# SPI_LCD_Backpack.net
KiCad netlist of a schematic drawn in EAGLE
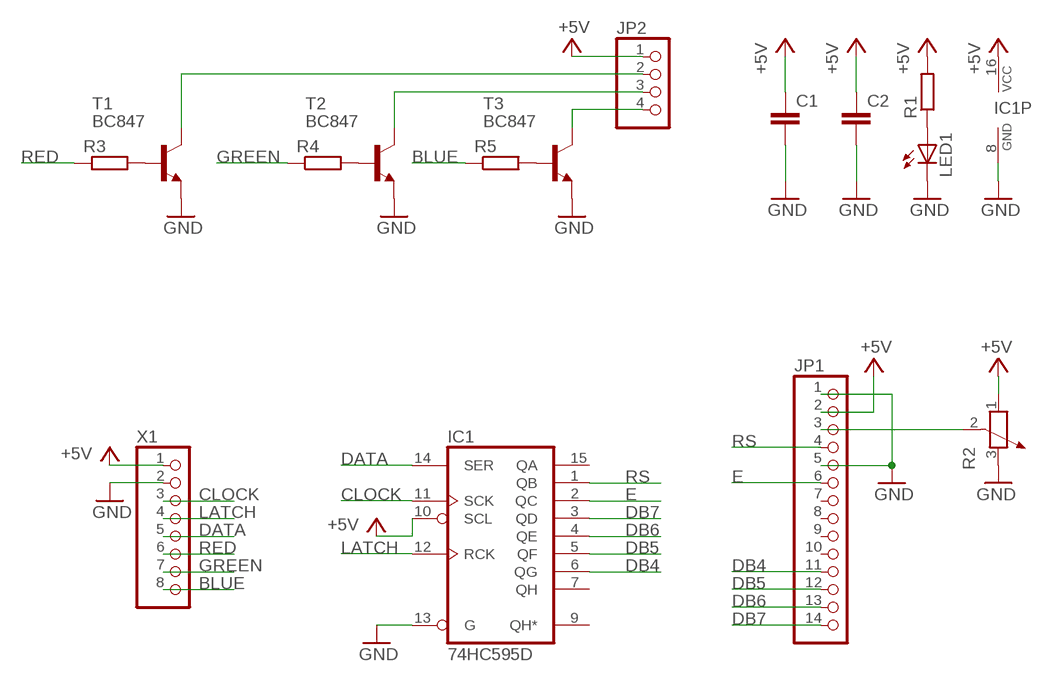
[diagram p0: schematic, sheet 1]

(export (version "E")
  (design (tool "Eeschema 10.0.6"))
  (components
    (comp (ref "C1")
      (value "C-EUC0805K")
      (footprint "eagle-import:C0805K")
      (libsource (lib "eagle-import") (part "C-EUC0805K"))
    )
    (comp (ref "C2")
      (value "C-EUC0805K")
      (footprint "eagle-import:C0805K")
      (libsource (lib "eagle-import") (part "C-EUC0805K"))
    )
    (comp (ref "IC1")
      (value "74HC595D")
      (footprint "eagle-import:SO16")
      (libsource (lib "eagle-import") (part "74595DHC"))
    )
    (comp (ref "JP1")
      (value "PINHD-1X14")
      (footprint "eagle-import:1X14")
      (libsource (lib "eagle-import") (part "PINHD-1X14"))
    )
    (comp (ref "JP2")
      (value "PINHD-1X4")
      (footprint "eagle-import:1X04")
      (libsource (lib "eagle-import") (part "PINHD-1X4"))
    )
    (comp (ref "LED1")
      (value "LED3MM")
      (footprint "eagle-import:LED3MM")
      (libsource (lib "eagle-import") (part "LED3MM"))
    )
    (comp (ref "R1")
      (value "R-EU_0805")
      (footprint "eagle-import:R0805")
      (libsource (lib "eagle-import") (part "R-EU_0805"))
    )
    (comp (ref "R2")
      (value "POTENTIOMETER_3386F")
      (footprint "eagle-import:3386F")
      (libsource (lib "eagle-import") (part "POTENTIOMETER_3386F"))
    )
    (comp (ref "R3")
      (value "R-EU_0805")
      (footprint "eagle-import:R0805")
      (libsource (lib "eagle-import") (part "R-EU_0805"))
    )
    (comp (ref "R4")
      (value "R-EU_0805")
      (footprint "eagle-import:R0805")
      (libsource (lib "eagle-import") (part "R-EU_0805"))
    )
    (comp (ref "R5")
      (value "R-EU_0805")
      (footprint "eagle-import:R0805")
      (libsource (lib "eagle-import") (part "R-EU_0805"))
    )
    (comp (ref "T1")
      (value "BC847")
      (footprint "eagle-import:SOT23")
      (libsource (lib "eagle-import") (part "BC847"))
    )
    (comp (ref "T2")
      (value "BC847")
      (footprint "eagle-import:SOT23")
      (libsource (lib "eagle-import") (part "BC847"))
    )
    (comp (ref "T3")
      (value "BC847")
      (footprint "eagle-import:SOT23")
      (libsource (lib "eagle-import") (part "BC847"))
    )
    (comp (ref "X1")
      (value "22-23-2081")
      (footprint "eagle-import:22-23-2081")
      (fields (field (name "MF") "MOLEX"))
      (libsource (lib "eagle-import") (part "22-23-2081"))
    )
  )
  (nets
    (net (code "1") (name "+5V") (class "Default")
      (node (ref "C1") (pin "1") (pinfunction "1_1") (pintype "passive"))
      (node (ref "C2") (pin "1") (pinfunction "1_1") (pintype "passive"))
      (node (ref "IC1") (pin "10") (pinfunction "SCL_10") (pintype "input"))
      (node (ref "IC1") (pin "16") (pinfunction "VCC_16") (pintype "power_in"))
      (node (ref "JP1") (pin "2") (pinfunction "2_2") (pintype "passive"))
      (node (ref "JP2") (pin "1") (pinfunction "1_1") (pintype "passive"))
      (node (ref "R1") (pin "2") (pinfunction "2_2") (pintype "passive"))
      (node (ref "R2") (pin "1") (pinfunction "1_1") (pintype "passive"))
      (node (ref "X1") (pin "1") (pinfunction "1_1") (pintype "passive"))
    )
    (net (code "2") (name "/BLUE") (class "Default")
      (node (ref "R5") (pin "1") (pinfunction "1_1") (pintype "passive"))
      (node (ref "X1") (pin "8") (pinfunction "8_8") (pintype "passive"))
    )
    (net (code "3") (name "/CLOCK") (class "Default")
      (node (ref "IC1") (pin "11") (pinfunction "SCK_11") (pintype "input"))
      (node (ref "X1") (pin "3") (pinfunction "3_3") (pintype "passive"))
    )
    (net (code "4") (name "/DATA") (class "Default")
      (node (ref "IC1") (pin "14") (pinfunction "SER_14") (pintype "input"))
      (node (ref "X1") (pin "5") (pinfunction "5_5") (pintype "passive"))
    )
    (net (code "5") (name "/DB4") (class "Default")
      (node (ref "IC1") (pin "6") (pinfunction "QG_6") (pintype "tri_state"))
      (node (ref "JP1") (pin "11") (pinfunction "11_11") (pintype "passive"))
    )
    (net (code "6") (name "/DB5") (class "Default")
      (node (ref "IC1") (pin "5") (pinfunction "QF_5") (pintype "tri_state"))
      (node (ref "JP1") (pin "12") (pinfunction "12_12") (pintype "passive"))
    )
    (net (code "7") (name "/DB6") (class "Default")
      (node (ref "IC1") (pin "4") (pinfunction "QE_4") (pintype "tri_state"))
      (node (ref "JP1") (pin "13") (pinfunction "13_13") (pintype "passive"))
    )
    (net (code "8") (name "/DB7") (class "Default")
      (node (ref "IC1") (pin "3") (pinfunction "QD_3") (pintype "tri_state"))
      (node (ref "JP1") (pin "14") (pinfunction "14_14") (pintype "passive"))
    )
    (net (code "9") (name "/E") (class "Default")
      (node (ref "IC1") (pin "2") (pinfunction "QC_2") (pintype "tri_state"))
      (node (ref "JP1") (pin "6") (pinfunction "6_6") (pintype "passive"))
    )
    (net (code "10") (name "/GREEN") (class "Default")
      (node (ref "R4") (pin "1") (pinfunction "1_1") (pintype "passive"))
      (node (ref "X1") (pin "7") (pinfunction "7_7") (pintype "passive"))
    )
    (net (code "11") (name "/LATCH") (class "Default")
      (node (ref "IC1") (pin "12") (pinfunction "RCK_12") (pintype "input"))
      (node (ref "X1") (pin "4") (pinfunction "4_4") (pintype "passive"))
    )
    (net (code "12") (name "/RED") (class "Default")
      (node (ref "R3") (pin "1") (pinfunction "1_1") (pintype "passive"))
      (node (ref "X1") (pin "6") (pinfunction "6_6") (pintype "passive"))
    )
    (net (code "13") (name "/RS") (class "Default")
      (node (ref "IC1") (pin "1") (pinfunction "QB_1") (pintype "tri_state"))
      (node (ref "JP1") (pin "4") (pinfunction "4_4") (pintype "passive"))
    )
    (net (code "14") (name "GND") (class "Default")
      (node (ref "C1") (pin "2") (pinfunction "2_2") (pintype "passive"))
      (node (ref "C2") (pin "2") (pinfunction "2_2") (pintype "passive"))
      (node (ref "IC1") (pin "13") (pinfunction "G_13") (pintype "input"))
      (node (ref "IC1") (pin "8") (pinfunction "GND_8") (pintype "power_in"))
      (node (ref "JP1") (pin "1") (pinfunction "1_1") (pintype "passive"))
      (node (ref "JP1") (pin "5") (pinfunction "5_5") (pintype "passive"))
      (node (ref "LED1") (pin "K") (pinfunction "C_K") (pintype "passive"))
      (node (ref "R2") (pin "3") (pinfunction "2_3") (pintype "passive"))
      (node (ref "T1") (pin "2") (pinfunction "E_2") (pintype "passive"))
      (node (ref "T2") (pin "2") (pinfunction "E_2") (pintype "passive"))
      (node (ref "T3") (pin "2") (pinfunction "E_2") (pintype "passive"))
      (node (ref "X1") (pin "2") (pinfunction "2_2") (pintype "passive"))
    )
    (net (code "15") (name "Net-(LED1-PadA)") (class "Default")
      (node (ref "LED1") (pin "A") (pinfunction "A_A") (pintype "passive"))
      (node (ref "R1") (pin "1") (pinfunction "1_1") (pintype "passive"))
    )
    (net (code "16") (name "Net-(R2-3)") (class "Default")
      (node (ref "JP1") (pin "3") (pinfunction "3_3") (pintype "passive"))
      (node (ref "R2") (pin "2") (pinfunction "3_2") (pintype "passive"))
    )
    (net (code "17") (name "Net-(T1-B)") (class "Default")
      (node (ref "R3") (pin "2") (pinfunction "2_2") (pintype "passive"))
      (node (ref "T1") (pin "1") (pinfunction "B_1") (pintype "passive"))
    )
    (net (code "18") (name "Net-(T1-C)") (class "Default")
      (node (ref "JP2") (pin "2") (pinfunction "2_2") (pintype "passive"))
      (node (ref "T1") (pin "3") (pinfunction "C_3") (pintype "passive"))
    )
    (net (code "19") (name "Net-(T2-B)") (class "Default")
      (node (ref "R4") (pin "2") (pinfunction "2_2") (pintype "passive"))
      (node (ref "T2") (pin "1") (pinfunction "B_1") (pintype "passive"))
    )
    (net (code "20") (name "Net-(T2-C)") (class "Default")
      (node (ref "JP2") (pin "3") (pinfunction "3_3") (pintype "passive"))
      (node (ref "T2") (pin "3") (pinfunction "C_3") (pintype "passive"))
    )
    (net (code "21") (name "Net-(T3-B)") (class "Default")
      (node (ref "R5") (pin "2") (pinfunction "2_2") (pintype "passive"))
      (node (ref "T3") (pin "1") (pinfunction "B_1") (pintype "passive"))
    )
    (net (code "22") (name "Net-(T3-C)") (class "Default")
      (node (ref "JP2") (pin "4") (pinfunction "4_4") (pintype "passive"))
      (node (ref "T3") (pin "3") (pinfunction "C_3") (pintype "passive"))
    )
    (net (code "23") (name "unconnected-(IC1A-QA-Pad15)") (class "Default")
      (node (ref "IC1") (pin "15") (pinfunction "QA_15") (pintype "tri_state"))
    )
    (net (code "24") (name "unconnected-(IC1A-QH*-Pad9)") (class "Default")
      (node (ref "IC1") (pin "9") (pinfunction "QH*_9") (pintype "tri_state"))
    )
    (net (code "25") (name "unconnected-(IC1A-QH-Pad7)") (class "Default")
      (node (ref "IC1") (pin "7") (pinfunction "QH_7") (pintype "tri_state"))
    )
    (net (code "26") (name "unconnected-(JP1-Pad7)") (class "Default")
      (node (ref "JP1") (pin "7") (pinfunction "7_7") (pintype "passive"))
    )
    (net (code "27") (name "unconnected-(JP1-Pad8)") (class "Default")
      (node (ref "JP1") (pin "8") (pinfunction "8_8") (pintype "passive"))
    )
    (net (code "28") (name "unconnected-(JP1-Pad9)") (class "Default")
      (node (ref "JP1") (pin "9") (pinfunction "9_9") (pintype "passive"))
    )
    (net (code "29") (name "unconnected-(JP1-Pad10)") (class "Default")
      (node (ref "JP1") (pin "10") (pinfunction "10_10") (pintype "passive"))
    )
  )
)
